# MKR1010_Barometer.net
KiCad netlist of a schematic drawn in EAGLE
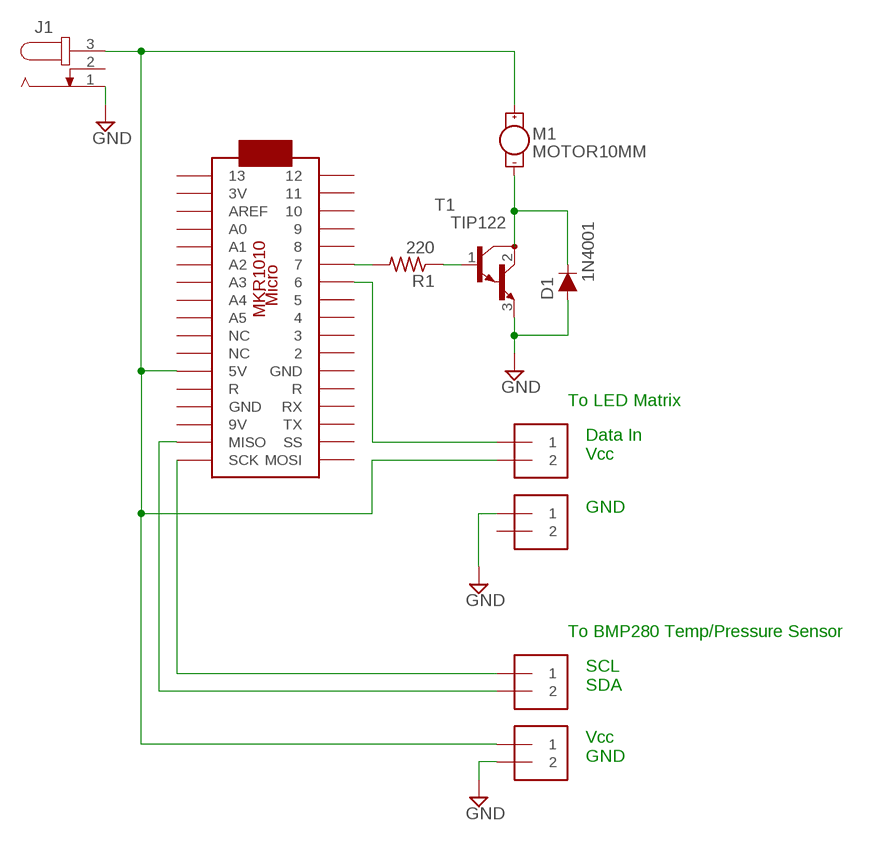
[diagram p0: schematic, sheet 1]

(export (version "E")
  (design (tool "Eeschema 10.0.6"))
  (components
    (comp (ref "D1")
      (value "1N4001")
      (footprint "eagle-import:DIODE-1N4001")
      (libsource (lib "eagle-import") (part "DIODE-PTH"))
    )
    (comp (ref "J1")
      (value "JACK-PLUG0")
      (footprint "eagle-import:SPC4077")
      (libsource (lib "eagle-import") (part "JACK-PLUG0"))
    )
    (comp (ref "J2")
      (value "1X2-3.5MM")
      (footprint "eagle-import:1X2-3.5MM")
      (libsource (lib "eagle-import") (part "1X2-3.5MM"))
    )
    (comp (ref "J3")
      (value "1X2-3.5MM")
      (footprint "eagle-import:1X2-3.5MM")
      (libsource (lib "eagle-import") (part "1X2-3.5MM"))
    )
    (comp (ref "J4")
      (value "1X2-3.5MM")
      (footprint "eagle-import:1X2-3.5MM")
      (libsource (lib "eagle-import") (part "1X2-3.5MM"))
    )
    (comp (ref "J5")
      (value "1X2-3.5MM")
      (footprint "eagle-import:1X2-3.5MM")
      (libsource (lib "eagle-import") (part "1X2-3.5MM"))
    )
    (comp (ref "M1")
      (value "MOTOR10MM")
      (footprint "eagle-import:VIBE-MOTOR-10MM")
      (libsource (lib "eagle-import") (part "MOTOR10MM"))
    )
    (comp (ref "MKR1010")
      (value "ARDUINOMICRO")
      (footprint "eagle-import:ARDUINOMICRO")
      (libsource (lib "eagle-import") (part "ARDUINOMICRO"))
    )
    (comp (ref "R1")
      (value "220")
      (footprint "eagle-import:0207_12")
      (libsource (lib "eagle-import") (part "R-US_0207/12"))
    )
    (comp (ref "T1")
      (value "TIP122")
      (footprint "eagle-import:TO220")
      (libsource (lib "eagle-import") (part "TIP122"))
    )
  )
  (nets
    (net (code "1") (name "GND") (class "Default")
      (node (ref "D1") (pin "A") (pinfunction "A_A") (pintype "passive"))
      (node (ref "J1") (pin "1") (pinfunction "1_1") (pintype "passive"))
      (node (ref "J3") (pin "1") (pinfunction "1_1") (pintype "passive"))
      (node (ref "J5") (pin "2") (pinfunction "2_2") (pintype "passive"))
      (node (ref "T1") (pin "3") (pinfunction "E_3") (pintype "passive"))
    )
    (net (code "2") (name "Net-(MKR1010-5V)") (class "Default")
      (node (ref "J1") (pin "3") (pinfunction "3_3") (pintype "passive"))
      (node (ref "J2") (pin "2") (pinfunction "2_2") (pintype "passive"))
      (node (ref "J5") (pin "1") (pinfunction "1_1") (pintype "passive"))
      (node (ref "M1") (pin "+") (pinfunction "+_+") (pintype "bidirectional"))
      (node (ref "MKR1010") (pin "P$23") (pinfunction "5V_P$23") (pintype "bidirectional"))
    )
    (net (code "3") (name "Net-(MKR1010-6)") (class "Default")
      (node (ref "J2") (pin "1") (pinfunction "1_1") (pintype "passive"))
      (node (ref "MKR1010") (pin "P$7") (pinfunction "6_P$7") (pintype "bidirectional"))
    )
    (net (code "4") (name "Net-(MKR1010-7)") (class "Default")
      (node (ref "MKR1010") (pin "P$6") (pinfunction "7_P$6") (pintype "bidirectional"))
      (node (ref "R1") (pin "2") (pinfunction "2_2") (pintype "passive"))
    )
    (net (code "5") (name "Net-(MKR1010-MISO)") (class "Default")
      (node (ref "J4") (pin "2") (pinfunction "2_2") (pintype "passive"))
      (node (ref "MKR1010") (pin "P$19") (pinfunction "MISO_P$19") (pintype "bidirectional"))
    )
    (net (code "6") (name "Net-(MKR1010-SCK)") (class "Default")
      (node (ref "J4") (pin "1") (pinfunction "1_1") (pintype "passive"))
      (node (ref "MKR1010") (pin "P$18") (pinfunction "SCK_P$18") (pintype "bidirectional"))
    )
    (net (code "7") (name "Net-(T1-B)") (class "Default")
      (node (ref "R1") (pin "1") (pinfunction "1_1") (pintype "passive"))
      (node (ref "T1") (pin "1") (pinfunction "B_1") (pintype "passive"))
    )
    (net (code "8") (name "Net-(T1-C)") (class "Default")
      (node (ref "D1") (pin "C") (pinfunction "C_C") (pintype "passive"))
      (node (ref "M1") (pin "-") (pinfunction "-_-") (pintype "bidirectional"))
      (node (ref "T1") (pin "2") (pinfunction "C_2") (pintype "passive"))
    )
    (net (code "9") (name "unconnected-(J1-Pad2)") (class "Default")
      (node (ref "J1") (pin "2") (pinfunction "2_2") (pintype "passive"))
    )
    (net (code "10") (name "unconnected-(J3-Pad2)") (class "Default")
      (node (ref "J3") (pin "2") (pinfunction "2_2") (pintype "passive"))
    )
    (net (code "11") (name "unconnected-(MKR1010-2-PadP$11)") (class "Default")
      (node (ref "MKR1010") (pin "P$11") (pinfunction "2_P$11") (pintype "bidirectional"))
    )
    (net (code "12") (name "unconnected-(MKR1010-3-PadP$10)") (class "Default")
      (node (ref "MKR1010") (pin "P$10") (pinfunction "3_P$10") (pintype "bidirectional"))
    )
    (net (code "13") (name "unconnected-(MKR1010-3V-PadP$33)") (class "Default")
      (node (ref "MKR1010") (pin "P$33") (pinfunction "3V_P$33") (pintype "bidirectional"))
    )
    (net (code "14") (name "unconnected-(MKR1010-4-PadP$9)") (class "Default")
      (node (ref "MKR1010") (pin "P$9") (pinfunction "4_P$9") (pintype "bidirectional"))
    )
    (net (code "15") (name "unconnected-(MKR1010-5-PadP$8)") (class "Default")
      (node (ref "MKR1010") (pin "P$8") (pinfunction "5_P$8") (pintype "bidirectional"))
    )
    (net (code "16") (name "unconnected-(MKR1010-8-PadP$5)") (class "Default")
      (node (ref "MKR1010") (pin "P$5") (pinfunction "8_P$5") (pintype "bidirectional"))
    )
    (net (code "17") (name "unconnected-(MKR1010-9-PadP$4)") (class "Default")
      (node (ref "MKR1010") (pin "P$4") (pinfunction "9_P$4") (pintype "bidirectional"))
    )
    (net (code "18") (name "unconnected-(MKR1010-9V-PadP$20)") (class "Default")
      (node (ref "MKR1010") (pin "P$20") (pinfunction "9V_P$20") (pintype "bidirectional"))
    )
    (net (code "19") (name "unconnected-(MKR1010-10-PadP$3)") (class "Default")
      (node (ref "MKR1010") (pin "P$3") (pinfunction "10_P$3") (pintype "bidirectional"))
    )
    (net (code "20") (name "unconnected-(MKR1010-11-PadP$2)") (class "Default")
      (node (ref "MKR1010") (pin "P$2") (pinfunction "11_P$2") (pintype "bidirectional"))
    )
    (net (code "21") (name "unconnected-(MKR1010-12-PadP$1)") (class "Default")
      (node (ref "MKR1010") (pin "P$1") (pinfunction "12_P$1") (pintype "bidirectional"))
    )
    (net (code "22") (name "unconnected-(MKR1010-13-PadP$34)") (class "Default")
      (node (ref "MKR1010") (pin "P$34") (pinfunction "13_P$34") (pintype "bidirectional"))
    )
    (net (code "23") (name "unconnected-(MKR1010-A0-PadP$31)") (class "Default")
      (node (ref "MKR1010") (pin "P$31") (pinfunction "A0_P$31") (pintype "bidirectional"))
    )
    (net (code "24") (name "unconnected-(MKR1010-A1-PadP$30)") (class "Default")
      (node (ref "MKR1010") (pin "P$30") (pinfunction "A1_P$30") (pintype "bidirectional"))
    )
    (net (code "25") (name "unconnected-(MKR1010-A2-PadP$29)") (class "Default")
      (node (ref "MKR1010") (pin "P$29") (pinfunction "A2_P$29") (pintype "bidirectional"))
    )
    (net (code "26") (name "unconnected-(MKR1010-A3-PadP$28)") (class "Default")
      (node (ref "MKR1010") (pin "P$28") (pinfunction "A3_P$28") (pintype "bidirectional"))
    )
    (net (code "27") (name "unconnected-(MKR1010-A4-PadP$27)") (class "Default")
      (node (ref "MKR1010") (pin "P$27") (pinfunction "A4_P$27") (pintype "bidirectional"))
    )
    (net (code "28") (name "unconnected-(MKR1010-A5-PadP$26)") (class "Default")
      (node (ref "MKR1010") (pin "P$26") (pinfunction "A5_P$26") (pintype "bidirectional"))
    )
    (net (code "29") (name "unconnected-(MKR1010-AREF-PadP$32)") (class "Default")
      (node (ref "MKR1010") (pin "P$32") (pinfunction "AREF_P$32") (pintype "bidirectional"))
    )
    (net (code "30") (name "unconnected-(MKR1010-GND-PadP$12)") (class "Default")
      (node (ref "MKR1010") (pin "P$12") (pinfunction "GND_P$12") (pintype "bidirectional"))
    )
    (net (code "31") (name "unconnected-(MKR1010-GND-PadP$21)") (class "Default")
      (node (ref "MKR1010") (pin "P$21") (pinfunction "GND_P$21") (pintype "bidirectional"))
    )
    (net (code "32") (name "unconnected-(MKR1010-MOSI-PadP$17)") (class "Default")
      (node (ref "MKR1010") (pin "P$17") (pinfunction "MOSI_P$17") (pintype "bidirectional"))
    )
    (net (code "33") (name "unconnected-(MKR1010-NC-PadP$24)") (class "Default")
      (node (ref "MKR1010") (pin "P$24") (pinfunction "NC_P$24") (pintype "bidirectional"))
    )
    (net (code "34") (name "unconnected-(MKR1010-NC-PadP$25)") (class "Default")
      (node (ref "MKR1010") (pin "P$25") (pinfunction "NC_P$25") (pintype "bidirectional"))
    )
    (net (code "35") (name "unconnected-(MKR1010-R-PadP$13)") (class "Default")
      (node (ref "MKR1010") (pin "P$13") (pinfunction "R_P$13") (pintype "bidirectional"))
    )
    (net (code "36") (name "unconnected-(MKR1010-R-PadP$22)") (class "Default")
      (node (ref "MKR1010") (pin "P$22") (pinfunction "R_P$22") (pintype "bidirectional"))
    )
    (net (code "37") (name "unconnected-(MKR1010-RX-PadP$14)") (class "Default")
      (node (ref "MKR1010") (pin "P$14") (pinfunction "RX_P$14") (pintype "bidirectional"))
    )
    (net (code "38") (name "unconnected-(MKR1010-SS-PadP$16)") (class "Default")
      (node (ref "MKR1010") (pin "P$16") (pinfunction "SS_P$16") (pintype "bidirectional"))
    )
    (net (code "39") (name "unconnected-(MKR1010-TX-PadP$15)") (class "Default")
      (node (ref "MKR1010") (pin "P$15") (pinfunction "TX_P$15") (pintype "bidirectional"))
    )
  )
)
